# billdetect_ring2b.net
KiCad netlist of a schematic drawn in EAGLE
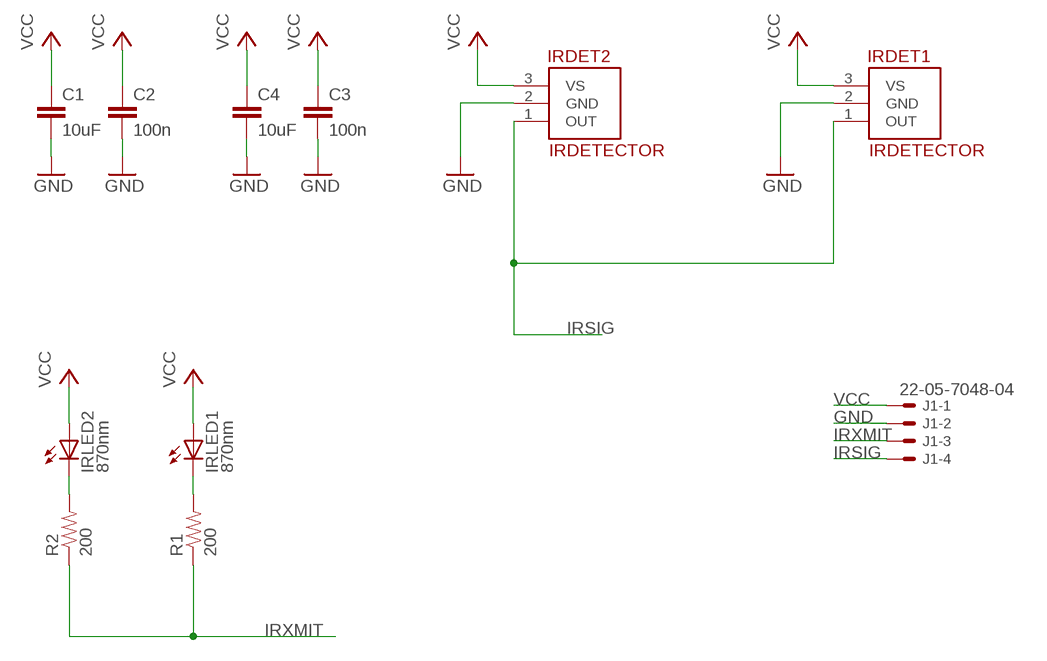
[diagram p0: schematic, sheet 1]

(export (version "E")
  (design (tool "Eeschema 10.0.6"))
  (components
    (comp (ref "C1")
      (value "10uF")
      (footprint "eagle-import:0805")
      (libsource (lib "eagle-import") (part "CAP0805"))
    )
    (comp (ref "C2")
      (value "100n")
      (footprint "eagle-import:0805")
      (libsource (lib "eagle-import") (part "CAP0805"))
    )
    (comp (ref "C3")
      (value "100n")
      (footprint "eagle-import:0805")
      (libsource (lib "eagle-import") (part "CAP0805"))
    )
    (comp (ref "C4")
      (value "10uF")
      (footprint "eagle-import:0805")
      (libsource (lib "eagle-import") (part "CAP0805"))
    )
    (comp (ref "IRDET1")
      (value "IRDETECTOR")
      (footprint "eagle-import:TSOP-3PIN-2.54MM")
      (libsource (lib "eagle-import") (part "IRDETECTOR"))
    )
    (comp (ref "IRDET2")
      (value "IRDETECTOR")
      (footprint "eagle-import:TSOP-3PIN-2.54MM")
      (libsource (lib "eagle-import") (part "IRDETECTOR"))
    )
    (comp (ref "IRLED1")
      (value "870nm")
      (footprint "eagle-import:LED-5MM-90DEG")
      (libsource (lib "eagle-import") (part "LED-5MM-90DEG"))
    )
    (comp (ref "IRLED2")
      (value "870nm")
      (footprint "eagle-import:LED-5MM-90DEG")
      (libsource (lib "eagle-import") (part "LED-5MM-90DEG"))
    )
    (comp (ref "J1")
      (value "22-05-7048-04")
      (footprint "eagle-import:7395-04")
      (libsource (lib "eagle-import") (part "22-?-0405-7048"))
    )
    (comp (ref "R1")
      (value "200")
      (footprint "eagle-import:0805")
      (libsource (lib "eagle-import") (part "RESISTOR0805-RES"))
    )
    (comp (ref "R2")
      (value "200")
      (footprint "eagle-import:0805")
      (libsource (lib "eagle-import") (part "RESISTOR0805-RES"))
    )
  )
  (nets
    (net (code "1") (name "/IRSIG") (class "Default")
      (node (ref "IRDET1") (pin "1") (pinfunction "OUT_1") (pintype "bidirectional"))
      (node (ref "IRDET2") (pin "1") (pinfunction "OUT_1") (pintype "bidirectional"))
      (node (ref "J1") (pin "4") (pinfunction "S_4") (pintype "passive"))
    )
    (net (code "2") (name "/IRXMIT") (class "Default")
      (node (ref "J1") (pin "3") (pinfunction "S_3") (pintype "passive"))
      (node (ref "R1") (pin "1") (pinfunction "1_1") (pintype "passive"))
      (node (ref "R2") (pin "1") (pinfunction "1_1") (pintype "passive"))
    )
    (net (code "3") (name "GND") (class "Default")
      (node (ref "C1") (pin "2") (pinfunction "2_2") (pintype "passive"))
      (node (ref "C2") (pin "2") (pinfunction "2_2") (pintype "passive"))
      (node (ref "C3") (pin "2") (pinfunction "2_2") (pintype "passive"))
      (node (ref "C4") (pin "2") (pinfunction "2_2") (pintype "passive"))
      (node (ref "IRDET1") (pin "2") (pinfunction "GND_2") (pintype "bidirectional"))
      (node (ref "IRDET2") (pin "2") (pinfunction "GND_2") (pintype "bidirectional"))
      (node (ref "J1") (pin "2") (pinfunction "S_2") (pintype "passive"))
    )
    (net (code "4") (name "Net-(IRLED1-C)") (class "Default")
      (node (ref "IRLED1") (pin "K") (pinfunction "C_K") (pintype "passive"))
      (node (ref "R1") (pin "2") (pinfunction "2_2") (pintype "passive"))
    )
    (net (code "5") (name "Net-(IRLED2-C)") (class "Default")
      (node (ref "IRLED2") (pin "K") (pinfunction "C_K") (pintype "passive"))
      (node (ref "R2") (pin "2") (pinfunction "2_2") (pintype "passive"))
    )
    (net (code "6") (name "VCC") (class "Default")
      (node (ref "C1") (pin "1") (pinfunction "1_1") (pintype "passive"))
      (node (ref "C2") (pin "1") (pinfunction "1_1") (pintype "passive"))
      (node (ref "C3") (pin "1") (pinfunction "1_1") (pintype "passive"))
      (node (ref "C4") (pin "1") (pinfunction "1_1") (pintype "passive"))
      (node (ref "IRDET1") (pin "3") (pinfunction "VS_3") (pintype "bidirectional"))
      (node (ref "IRDET2") (pin "3") (pinfunction "VS_3") (pintype "bidirectional"))
      (node (ref "IRLED1") (pin "A") (pinfunction "A_A") (pintype "passive"))
      (node (ref "IRLED2") (pin "A") (pinfunction "A_A") (pintype "passive"))
      (node (ref "J1") (pin "1") (pinfunction "S_1") (pintype "passive"))
    )
  )
)
